# SCH_NFC-CARD-Christina_2024-10-21.net
KiCad netlist of a schematic drawn in EasyEDA
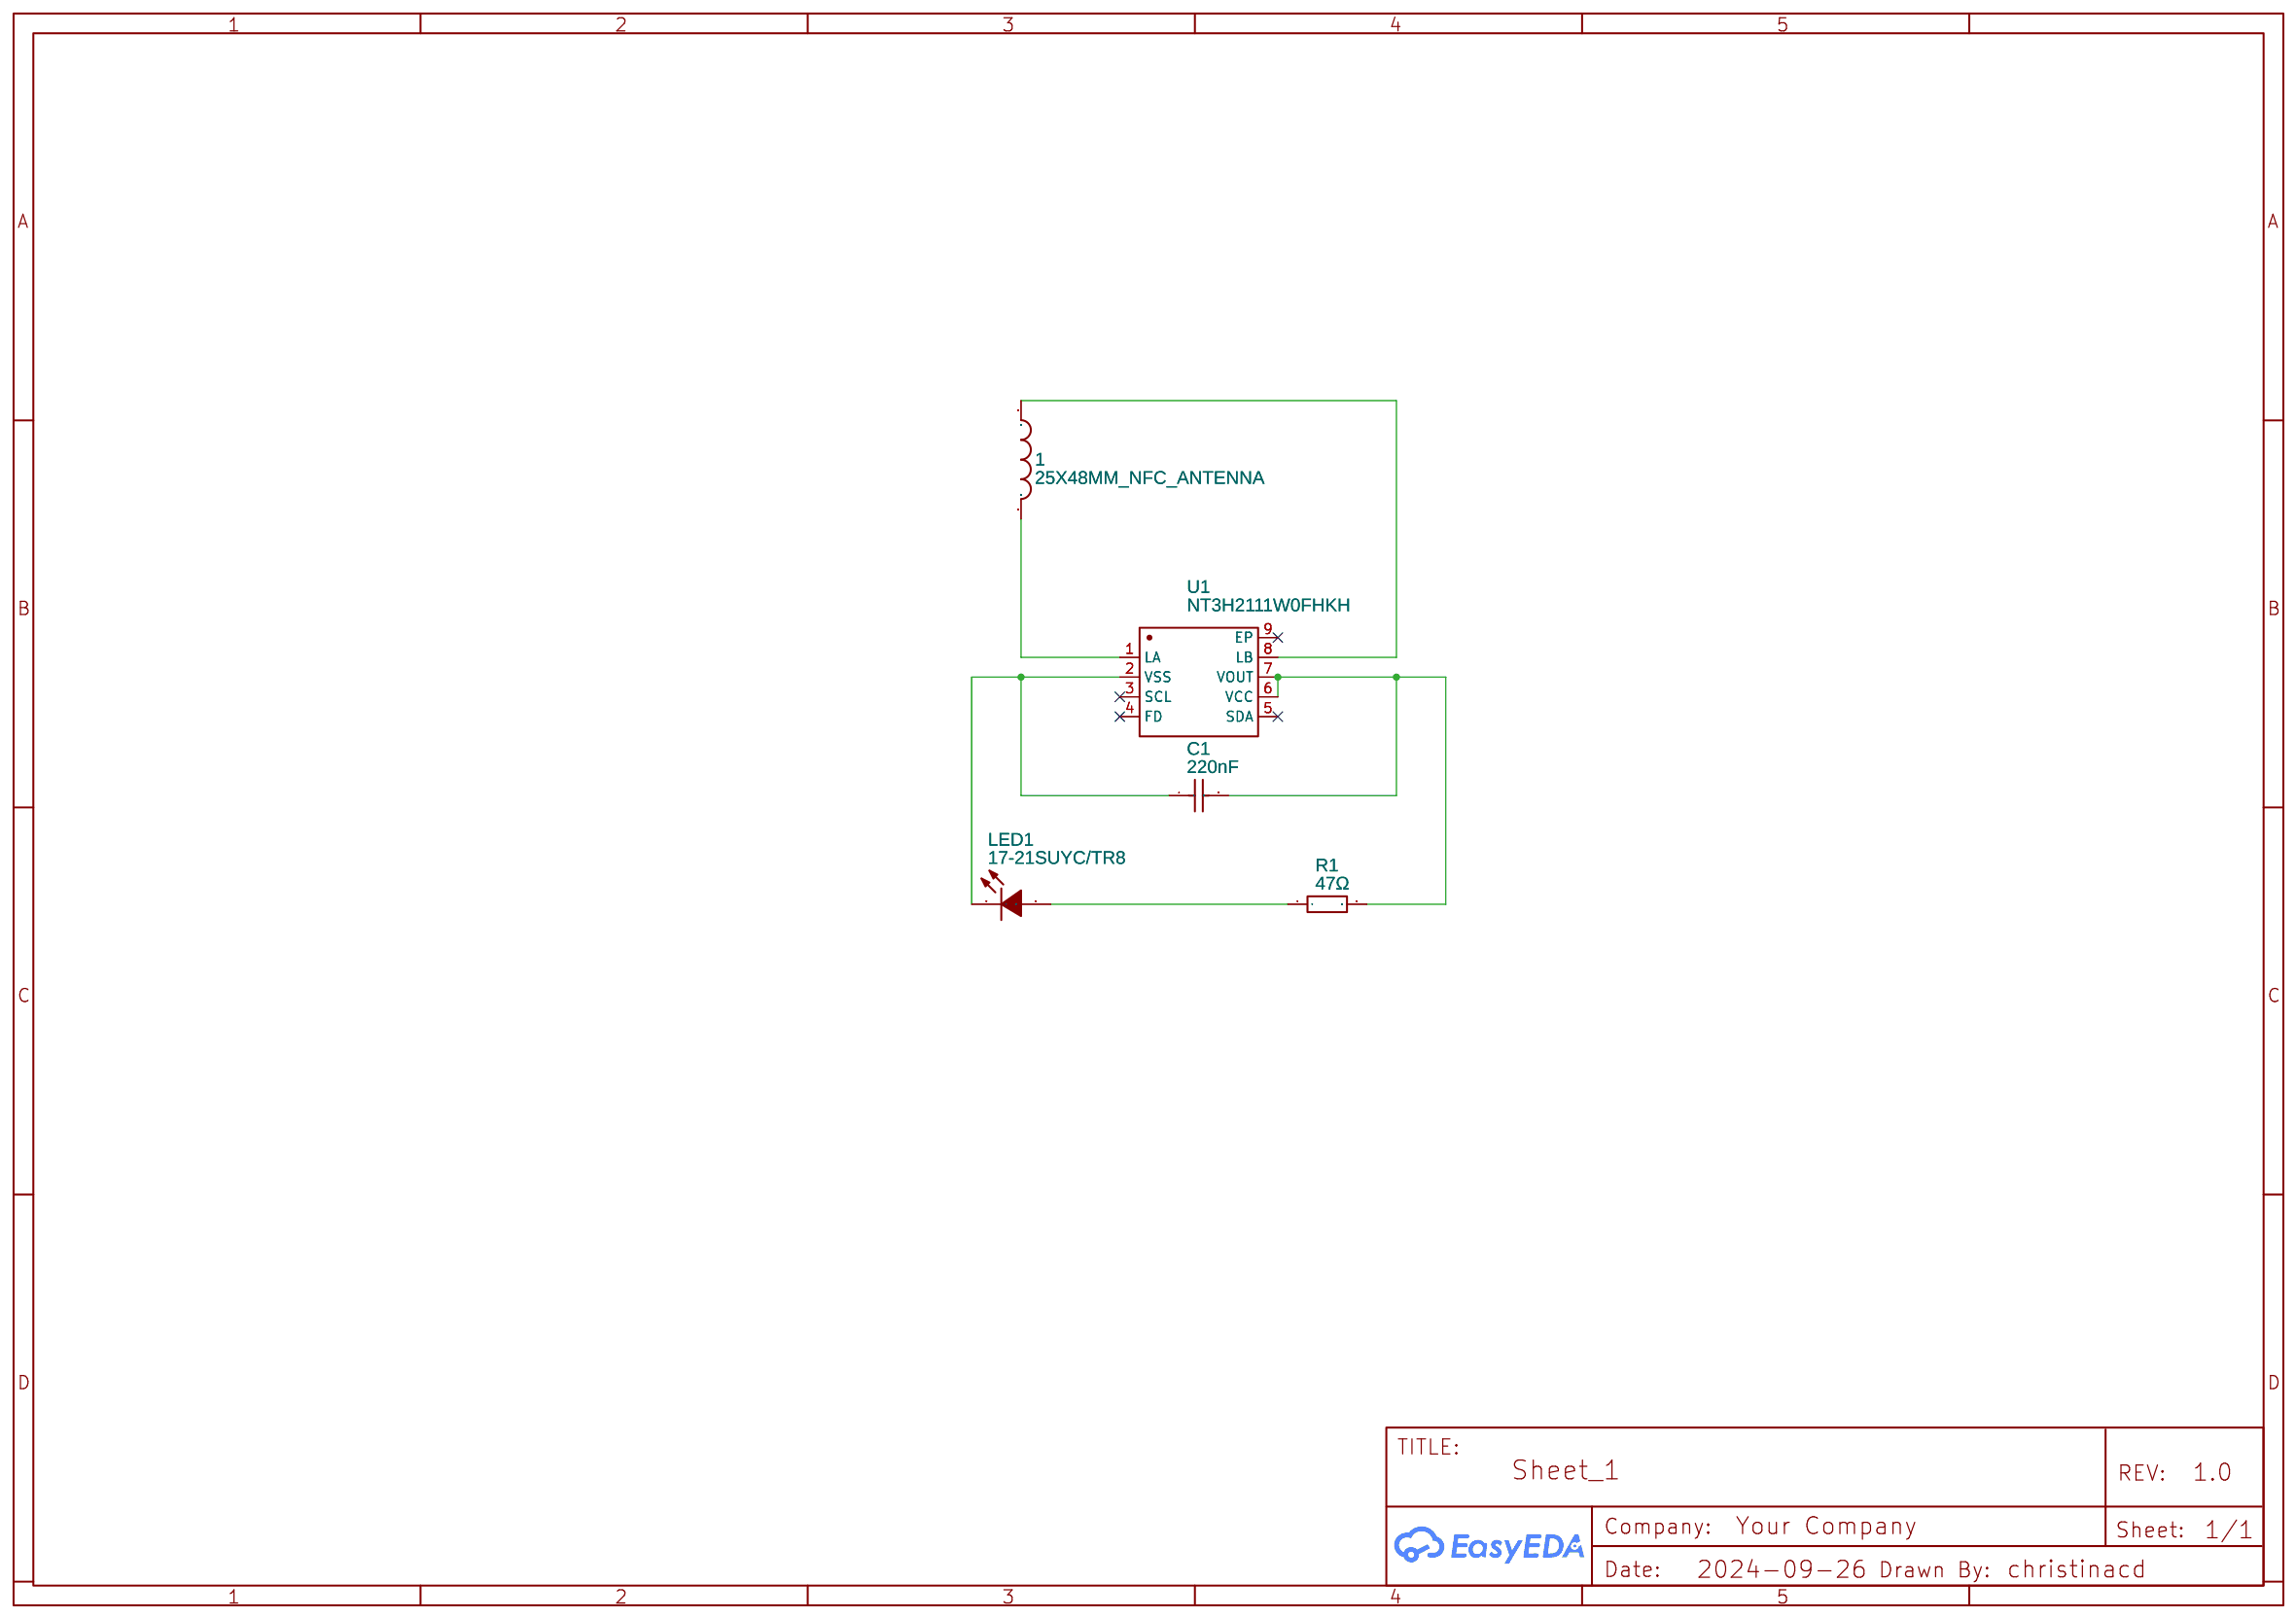
[diagram p0: schematic sheet]

(export (version "E")
  (design (tool "Eeschema 10.0.6"))
  (components
    (comp (ref "1") (value "25X48MM_NFC_ANTENNA") (libsource (lib "") (part "25X48MM_NFC_ANTENNA")))
    (comp (ref "C1")
      (value "220nF")
      (fields
        (field (name "Manufacturer Part") "CL10B224KA8NNNC")
        (field (name "Manufacturer") "SAMSUNG(三星)")
      )
      (libsource (lib "") (part "CL10B224KA8NNNC"))
    )
    (comp (ref "LED1")
      (value "17-21SUYC/TR8")
      (fields (field (name "Manufacturer Part") "KT-0805黄灯") (field (name "Manufacturer") "KENTO"))
      (libsource (lib "") (part "17-21SUYC/TR8"))
    )
    (comp (ref "R1")
      (value "47Ω")
      (fields
        (field (name "Manufacturer Part") "0603WAF470JT5E")
        (field (name "Manufacturer") "UNI-ROYAL(厚声)")
      )
      (libsource (lib "") (part "0603WAF470JT5E"))
    )
    (comp (ref "U1")
      (value "NT3H2111W0FHKH")
      (fields (field (name "Manufacturer") "NXP(恩智浦)"))
      (libsource (lib "") (part "NT3H2111W0FHKH"))
    )
  )
  (nets
    (net (code "1") (name "Net-(LED1-+)") (class "Default")
      (node (ref "LED1") (pin "1") (pinfunction "+_1") (pintype "unspecified"))
      (node (ref "R1") (pin "1") (pinfunction "1_1") (pintype "input"))
    )
    (net (code "2") (name "Net-(LED1--)") (class "Default")
      (node (ref "C1") (pin "1") (pinfunction "1_1") (pintype "input"))
      (node (ref "LED1") (pin "2") (pinfunction "-_2") (pintype "unspecified"))
      (node (ref "U1") (pin "2") (pinfunction "VSS_2") (pintype "unspecified"))
    )
    (net (code "3") (name "Net-(U1-LA)") (class "Default")
      (node (ref "1") (pin "P$2") (pinfunction "P$2_P$2") (pintype "bidirectional"))
      (node (ref "U1") (pin "1") (pinfunction "LA_1") (pintype "unspecified"))
    )
    (net (code "4") (name "Net-(U1-LB)") (class "Default")
      (node (ref "1") (pin "P$1") (pinfunction "P$1_P$1") (pintype "bidirectional"))
      (node (ref "U1") (pin "8") (pinfunction "LB_8") (pintype "unspecified"))
    )
    (net (code "5") (name "Net-(U1-VCC)") (class "Default")
      (node (ref "C1") (pin "2") (pinfunction "2_2") (pintype "input"))
      (node (ref "R1") (pin "2") (pinfunction "2_2") (pintype "input"))
      (node (ref "U1") (pin "6") (pinfunction "VCC_6") (pintype "unspecified"))
      (node (ref "U1") (pin "7") (pinfunction "VOUT_7") (pintype "unspecified"))
    )
    (net (code "6") (name "unconnected-(U1-EP-Pad9)") (class "Default")
      (node (ref "U1") (pin "9") (pinfunction "EP_9") (pintype "unspecified+no_connect"))
    )
    (net (code "7") (name "unconnected-(U1-FD-Pad4)") (class "Default")
      (node (ref "U1") (pin "4") (pinfunction "FD_4") (pintype "unspecified+no_connect"))
    )
    (net (code "8") (name "unconnected-(U1-SCL-Pad3)") (class "Default")
      (node (ref "U1") (pin "3") (pinfunction "SCL_3") (pintype "unspecified+no_connect"))
    )
    (net (code "9") (name "unconnected-(U1-SDA-Pad5)") (class "Default")
      (node (ref "U1") (pin "5") (pinfunction "SDA_5") (pintype "unspecified+no_connect"))
    )
  )
)
